# BANK0.net
KiCad netlist of a schematic drawn in Altium Designer
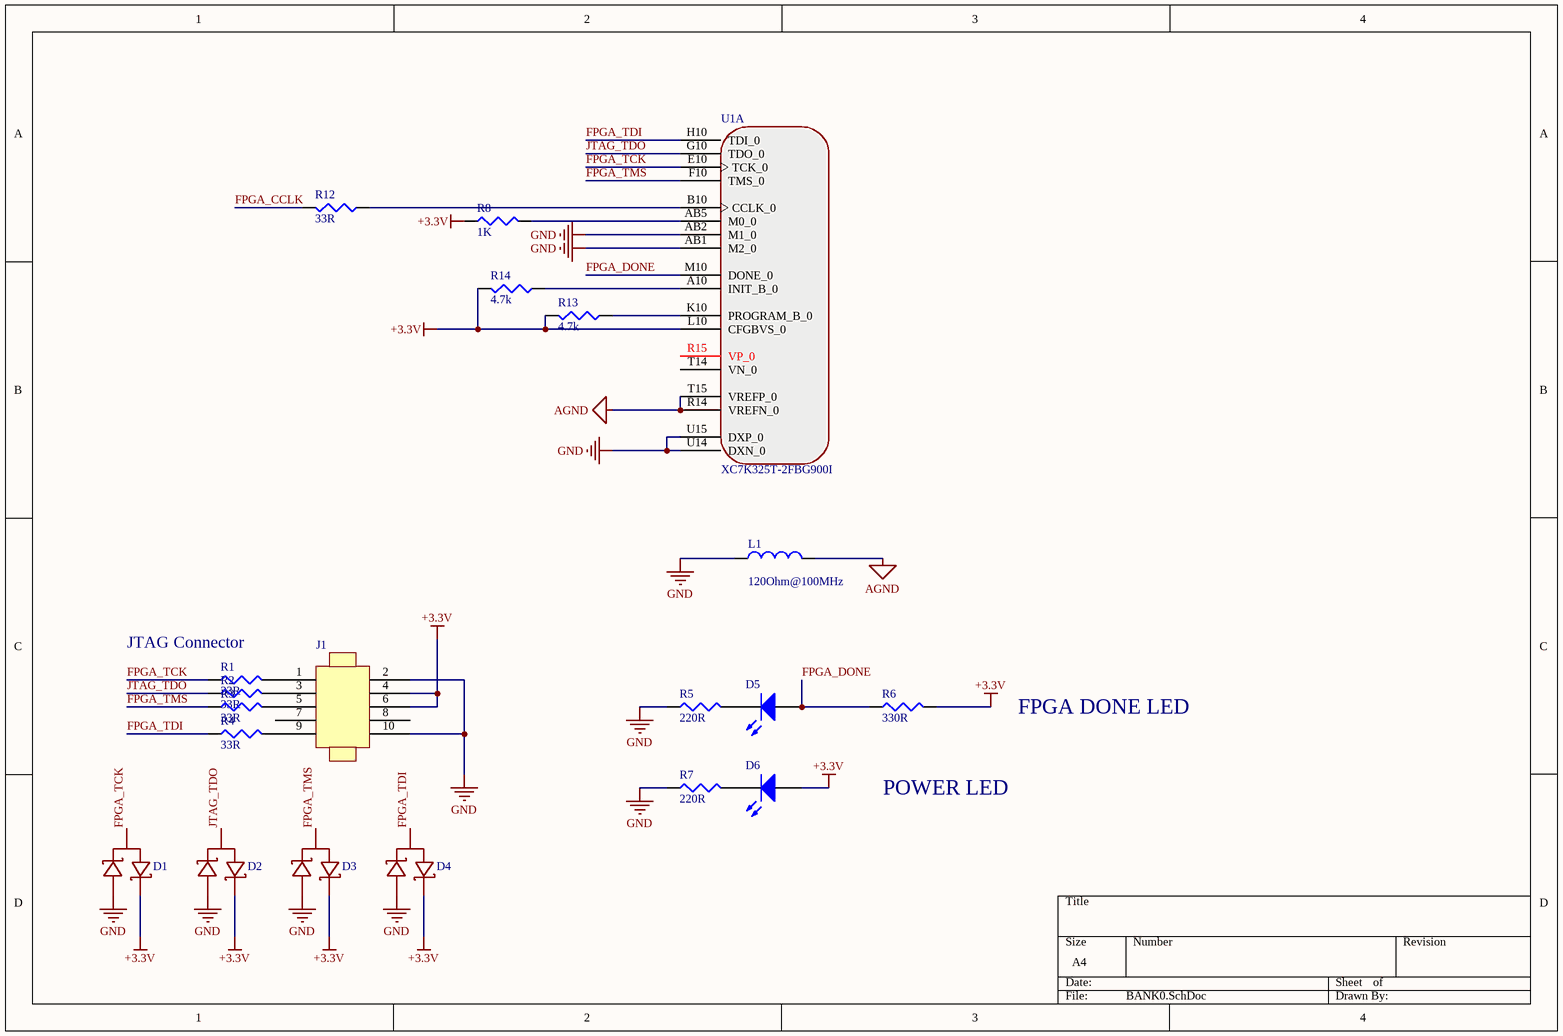
[diagram p0: BANK0.SchDoc]

(export (version "E")
  (design (tool "Eeschema 10.0.6"))
  (components
    (comp (ref "D1") (value "BAT5S") (footprint "SOT-23") (libsource (lib "Schlib1") (part "BAT5S")))
    (comp (ref "D2") (value "BAT5S") (footprint "SOT-23") (libsource (lib "Schlib1") (part "BAT5S")))
    (comp (ref "D3") (value "BAT5S") (footprint "SOT-23") (libsource (lib "Schlib1") (part "BAT5S")))
    (comp (ref "D4") (value "BAT5S") (footprint "SOT-23") (libsource (lib "Schlib1") (part "BAT5S")))
    (comp (ref "D5")
      (value "LED3")
      (footprint "3.5X2.8X1.9")
      (description "Typical BLUE SiC LED")
      (fields (field (name "PUBLISHER") "Altium Limited"))
      (libsource (lib "Miscellaneous Devices") (part "LED3"))
    )
    (comp (ref "D6")
      (value "LED3")
      (footprint "3.5X2.8X1.9")
      (description "Typical BLUE SiC LED")
      (fields (field (name "PUBLISHER") "Altium Limited"))
      (libsource (lib "Miscellaneous Devices") (part "LED3"))
    )
    (comp (ref "J1") (value "JTAG-10") (footprint "JTAG-10") (libsource (lib "Schlib1") (part "JTAG-10")))
    (comp (ref "L1")
      (value "120Ohm@100MHz")
      (footprint "0402-A")
      (description "Inductor")
      (fields (field (name "PUBLISHER") "Altium Limited"))
      (libsource (lib "Miscellaneous Devices") (part "Inductor"))
    )
    (comp (ref "R1")
      (value "33R")
      (footprint "J1-0603")
      (description "Resistor")
      (fields (field (name "Comment") "Res3") (field (name "PUBLISHER") "Altium Limited"))
      (libsource (lib "Miscellaneous Devices") (part "Res3"))
    )
    (comp (ref "R2")
      (value "33R")
      (footprint "J1-0603")
      (description "Resistor")
      (fields (field (name "Comment") "Res3") (field (name "PUBLISHER") "Altium Limited"))
      (libsource (lib "Miscellaneous Devices") (part "Res3"))
    )
    (comp (ref "R3")
      (value "33R")
      (footprint "J1-0603")
      (description "Resistor")
      (fields (field (name "Comment") "Res3") (field (name "PUBLISHER") "Altium Limited"))
      (libsource (lib "Miscellaneous Devices") (part "Res3"))
    )
    (comp (ref "R4")
      (value "33R")
      (footprint "J1-0603")
      (description "Resistor")
      (fields (field (name "Comment") "Res3") (field (name "PUBLISHER") "Altium Limited"))
      (libsource (lib "Miscellaneous Devices") (part "Res3"))
    )
    (comp (ref "R5")
      (value "220R")
      (footprint "J1-0603")
      (description "Resistor")
      (fields (field (name "Comment") "Res3") (field (name "PUBLISHER") "Altium Limited"))
      (libsource (lib "Miscellaneous Devices") (part "Res3"))
    )
    (comp (ref "R6")
      (value "330R")
      (footprint "J1-0603")
      (description "Resistor")
      (fields (field (name "Comment") "Res3") (field (name "PUBLISHER") "Altium Limited"))
      (libsource (lib "Miscellaneous Devices") (part "Res3"))
    )
    (comp (ref "R7")
      (value "220R")
      (footprint "J1-0603")
      (description "Resistor")
      (fields (field (name "Comment") "Res3") (field (name "PUBLISHER") "Altium Limited"))
      (libsource (lib "Miscellaneous Devices") (part "Res3"))
    )
    (comp (ref "R8")
      (value "1K")
      (footprint "J1-0603")
      (description "Resistor")
      (fields (field (name "Comment") "Res3") (field (name "PUBLISHER") "Altium Limited"))
      (libsource (lib "Miscellaneous Devices") (part "Res3"))
    )
    (comp (ref "R12")
      (value "33R")
      (footprint "J1-0603")
      (description "Resistor")
      (fields (field (name "Comment") "Res3") (field (name "PUBLISHER") "Altium Limited"))
      (libsource (lib "Miscellaneous Devices") (part "Res3"))
    )
    (comp (ref "R13")
      (value "4.7k")
      (footprint "J1-0603")
      (description "Resistor")
      (fields (field (name "Comment") "Res3") (field (name "PUBLISHER") "Altium Limited"))
      (libsource (lib "Miscellaneous Devices") (part "Res3"))
    )
    (comp (ref "R14")
      (value "4.7k")
      (footprint "J1-0603")
      (description "Resistor")
      (fields (field (name "Comment") "Res3") (field (name "PUBLISHER") "Altium Limited"))
      (libsource (lib "Miscellaneous Devices") (part "Res3"))
    )
    (comp (ref "U1")
      (value "XC7K325T-2FBG900I")
      (footprint "FBG900")
      (libsource (lib "Schlib1") (part "XC7K325T-2FBG900I"))
    )
  )
  (nets
    (net (code "1") (name "+3.3V") (class "Default")
      (node (ref "D1") (pin "2") (pinfunction "K2_2") (pintype "passive"))
      (node (ref "D2") (pin "2") (pinfunction "K2_2") (pintype "passive"))
      (node (ref "D3") (pin "2") (pinfunction "K2_2") (pintype "passive"))
      (node (ref "D4") (pin "2") (pinfunction "K2_2") (pintype "passive"))
      (node (ref "D6") (pin "1") (pinfunction "A_1") (pintype "passive"))
      (node (ref "J1") (pin "4") (pinfunction "4_4") (pintype "passive"))
      (node (ref "J1") (pin "6") (pinfunction "6_6") (pintype "passive"))
      (node (ref "R13") (pin "2") (pinfunction "2_2") (pintype "passive"))
      (node (ref "R14") (pin "2") (pinfunction "2_2") (pintype "passive"))
      (node (ref "R6") (pin "2") (pinfunction "2_2") (pintype "passive"))
      (node (ref "R8") (pin "1") (pinfunction "1_1") (pintype "passive"))
      (node (ref "U1") (pin "L10") (pinfunction "CFGBVS_0_L10") (pintype "passive"))
    )
    (net (code "2") (name "/FPGA_CCLK") (class "Default")
      (node (ref "R12") (pin "2") (pinfunction "2_2") (pintype "passive"))
    )
    (net (code "3") (name "/FPGA_DONE") (class "Default")
      (node (ref "D5") (pin "1") (pinfunction "A_1") (pintype "passive"))
      (node (ref "R6") (pin "1") (pinfunction "1_1") (pintype "passive"))
      (node (ref "U1") (pin "M10") (pinfunction "DONE_0_M10") (pintype "passive"))
    )
    (net (code "4") (name "/FPGA_TCK") (class "Default")
      (node (ref "D1") (pin "3") (pinfunction "A_3") (pintype "passive"))
      (node (ref "R1") (pin "1") (pinfunction "1_1") (pintype "passive"))
      (node (ref "U1") (pin "E10") (pinfunction "TCK_0_E10") (pintype "passive"))
    )
    (net (code "5") (name "/FPGA_TDI") (class "Default")
      (node (ref "D4") (pin "3") (pinfunction "A_3") (pintype "passive"))
      (node (ref "R4") (pin "1") (pinfunction "1_1") (pintype "passive"))
      (node (ref "U1") (pin "H10") (pinfunction "TDI_0_H10") (pintype "passive"))
    )
    (net (code "6") (name "/FPGA_TMS") (class "Default")
      (node (ref "D3") (pin "3") (pinfunction "A_3") (pintype "passive"))
      (node (ref "R3") (pin "1") (pinfunction "1_1") (pintype "passive"))
      (node (ref "U1") (pin "F10") (pinfunction "TMS_0_F10") (pintype "passive"))
    )
    (net (code "7") (name "/JTAG_TDO") (class "Default")
      (node (ref "D2") (pin "3") (pinfunction "A_3") (pintype "passive"))
      (node (ref "R2") (pin "1") (pinfunction "1_1") (pintype "passive"))
      (node (ref "U1") (pin "G10") (pinfunction "TDO_0_G10") (pintype "passive"))
    )
    (net (code "8") (name "AGND") (class "Default")
      (node (ref "L1") (pin "2") (pinfunction "2_2") (pintype "passive"))
      (node (ref "U1") (pin "R14") (pinfunction "VREFN_0_R14") (pintype "passive"))
      (node (ref "U1") (pin "T15") (pinfunction "VREFP_0_T15") (pintype "passive"))
    )
    (net (code "9") (name "GND") (class "Default")
      (node (ref "D1") (pin "1") (pinfunction "A1_1") (pintype "passive"))
      (node (ref "D2") (pin "1") (pinfunction "A1_1") (pintype "passive"))
      (node (ref "D3") (pin "1") (pinfunction "A1_1") (pintype "passive"))
      (node (ref "D4") (pin "1") (pinfunction "A1_1") (pintype "passive"))
      (node (ref "J1") (pin "10") (pinfunction "10_10") (pintype "passive"))
      (node (ref "J1") (pin "2") (pinfunction "2_2") (pintype "passive"))
      (node (ref "L1") (pin "1") (pinfunction "1_1") (pintype "passive"))
      (node (ref "R5") (pin "1") (pinfunction "1_1") (pintype "passive"))
      (node (ref "R7") (pin "1") (pinfunction "1_1") (pintype "passive"))
      (node (ref "U1") (pin "AB1") (pinfunction "M2_0_AB1") (pintype "passive"))
      (node (ref "U1") (pin "AB2") (pinfunction "M1_0_AB2") (pintype "passive"))
      (node (ref "U1") (pin "U14") (pinfunction "DXN_0_U14") (pintype "passive"))
      (node (ref "U1") (pin "U15") (pinfunction "DXP_0_U15") (pintype "passive"))
    )
    (net (code "10") (name "Net-(D5-K)") (class "Default")
      (node (ref "D5") (pin "2") (pinfunction "K_2") (pintype "passive"))
      (node (ref "R5") (pin "2") (pinfunction "2_2") (pintype "passive"))
    )
    (net (code "11") (name "Net-(D6-K)") (class "Default")
      (node (ref "D6") (pin "2") (pinfunction "K_2") (pintype "passive"))
      (node (ref "R7") (pin "2") (pinfunction "2_2") (pintype "passive"))
    )
    (net (code "12") (name "Net-(J1-Pad1)") (class "Default")
      (node (ref "J1") (pin "1") (pinfunction "1_1") (pintype "passive"))
      (node (ref "R1") (pin "2") (pinfunction "2_2") (pintype "passive"))
    )
    (net (code "13") (name "Net-(J1-Pad3)") (class "Default")
      (node (ref "J1") (pin "3") (pinfunction "3_3") (pintype "passive"))
      (node (ref "R2") (pin "2") (pinfunction "2_2") (pintype "passive"))
    )
    (net (code "14") (name "Net-(J1-Pad5)") (class "Default")
      (node (ref "J1") (pin "5") (pinfunction "5_5") (pintype "passive"))
      (node (ref "R3") (pin "2") (pinfunction "2_2") (pintype "passive"))
    )
    (net (code "15") (name "Net-(J1-Pad9)") (class "Default")
      (node (ref "J1") (pin "9") (pinfunction "9_9") (pintype "passive"))
      (node (ref "R4") (pin "2") (pinfunction "2_2") (pintype "passive"))
    )
    (net (code "16") (name "Net-(U1A-CCLK_0)") (class "Default")
      (node (ref "R12") (pin "1") (pinfunction "1_1") (pintype "passive"))
      (node (ref "U1") (pin "B10") (pinfunction "CCLK_0_B10") (pintype "passive"))
    )
    (net (code "17") (name "Net-(U1A-INIT_B_0)") (class "Default")
      (node (ref "R14") (pin "1") (pinfunction "1_1") (pintype "passive"))
      (node (ref "U1") (pin "A10") (pinfunction "INIT_B_0_A10") (pintype "passive"))
    )
    (net (code "18") (name "Net-(U1A-M0_0)") (class "Default")
      (node (ref "R8") (pin "2") (pinfunction "2_2") (pintype "passive"))
      (node (ref "U1") (pin "AB5") (pinfunction "M0_0_AB5") (pintype "passive"))
    )
    (net (code "19") (name "Net-(U1A-PROGRAM_B_0)") (class "Default")
      (node (ref "R13") (pin "1") (pinfunction "1_1") (pintype "passive"))
      (node (ref "U1") (pin "K10") (pinfunction "PROGRAM_B_0_K10") (pintype "passive"))
    )
    (net (code "20") (name "unconnected-(J1-Pad7)") (class "Default")
      (node (ref "J1") (pin "7") (pinfunction "7_7") (pintype "passive"))
    )
    (net (code "21") (name "unconnected-(J1-Pad8)") (class "Default")
      (node (ref "J1") (pin "8") (pinfunction "8_8") (pintype "passive"))
    )
    (net (code "22") (name "unconnected-(U1A-VN_0-PadT14)") (class "Default")
      (node (ref "U1") (pin "T14") (pinfunction "VN_0_T14") (pintype "passive"))
    )
    (net (code "23") (name "unconnected-(U1A-VP_0-PadR15)") (class "Default")
      (node (ref "U1") (pin "R15") (pinfunction "VP_0_R15") (pintype "passive"))
    )
  )
)
